# Main.net
KiCad netlist of a schematic drawn in Altium Designer
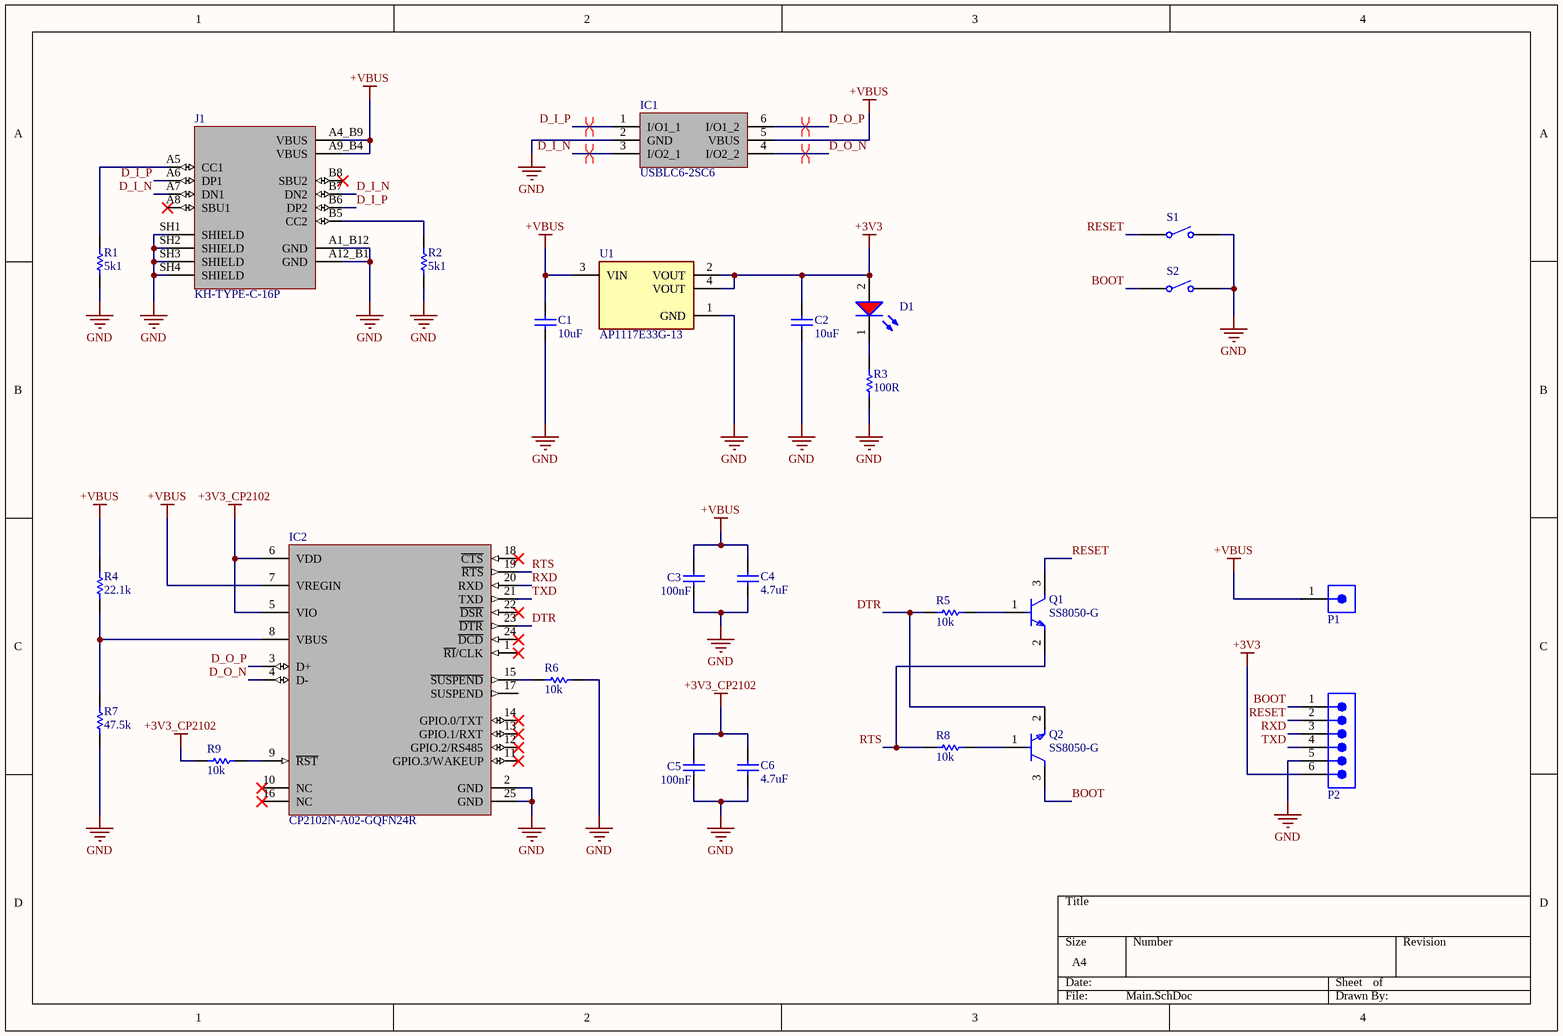
[diagram p0: Main.SchDoc]

(export (version "E")
  (design (tool "Eeschema 10.0.6"))
  (components
    (comp (ref "C1")
      (value "10uF")
      (footprint "Wurth 0603 capacitor")
      (fields (field (name "Comment") "Generic Capacitor 10uF 0603"))
      (libsource (lib "Passives") (part "Generic Capacitor 10uF 0603"))
    )
    (comp (ref "C2")
      (value "10uF")
      (footprint "Wurth 0603 capacitor")
      (fields (field (name "Comment") "Generic Capacitor 10uF 0603"))
      (libsource (lib "Passives") (part "Generic Capacitor 10uF 0603"))
    )
    (comp (ref "C3")
      (value "100nF")
      (footprint "Wurth 0603 capacitor")
      (fields (field (name "Comment") "Generic Capacitor 100nF 0603"))
      (libsource (lib "Passives") (part "Generic Capacitor 100nF 0603"))
    )
    (comp (ref "C4")
      (value "4.7uF")
      (footprint "Wurth 0603 capacitor")
      (fields (field (name "Comment") "Generic Capacitor 4.7uF 0603"))
      (libsource (lib "Passives") (part "Generic Capacitor 4.7uF 0603"))
    )
    (comp (ref "C5")
      (value "100nF")
      (footprint "Wurth 0603 capacitor")
      (fields (field (name "Comment") "Generic Capacitor 100nF 0603"))
      (libsource (lib "Passives") (part "Generic Capacitor 100nF 0603"))
    )
    (comp (ref "C6")
      (value "4.7uF")
      (footprint "Wurth 0603 capacitor")
      (fields (field (name "Comment") "Generic Capacitor 4.7uF 0603"))
      (libsource (lib "Passives") (part "Generic Capacitor 4.7uF 0603"))
    )
    (comp (ref "D1")
      (value "150060RS75000")
      (footprint "WL-SMCW_0603_150060xx75000")
      (libsource (lib "Altium Content Vault") (part "LED_Red_2A-1K"))
    )
    (comp (ref "IC1")
      (value "USBLC6-2SC6")
      (footprint "Tech Public SOT23-6")
      (description "Integrated Circuit")
      (fields (field (name "MOUSER PART NUMBER") "511-USBLC6-2SC6"))
      (libsource (lib "Diodes") (part "Tech Public USBLC6-2SC6"))
    )
    (comp (ref "IC2")
      (value "CP2102N-A02-GQFN24R")
      (footprint "Leadless:FP-CP2102N-A02-GQFN24R-IPC_C")
      (description "IC USB TO UART BRIDGE QFN24")
      (libsource (lib "USB_Controllers") (part "Silicon Labs CP2102N-A02-GQFN24R"))
    )
    (comp (ref "J1")
      (value "KH-TYPE-C-16P")
      (footprint "KINGHELM_KH-TYPE-C-16P")
      (fields (field (name "MF") "kinghelm"))
      (libsource (lib "Connectors") (part "KH-TYPE-C-16P"))
    )
    (comp (ref "P1")
      (value "61300111121")
      (footprint "1x1 2.54mm M")
      (description "WR-PHD Pin Header, THT, Vertical, pitch 2.54mm, 1 Row, 1P")
      (fields (field (name "MANUFACTURER") "Wurth Elektronik"))
      (libsource (lib "2.54mm_pin_headers") (part "1P"))
    )
    (comp (ref "P2")
      (value "61300611121")
      (footprint "6x1 2.54mm M")
      (description "WR-PHD Pin Header, THT, Vertical, pitch 2.54mm, 1 Row, 6P")
      (fields (field (name "MANUFACTURER") "Wurth Elektronik"))
      (libsource (lib "2.54mm_pin_headers") (part "6P"))
    )
    (comp (ref "Q1")
      (value "SS8050-G")
      (footprint "FP-SS8050-G-MFG")
      (description "NPN TRANSISTOR 1.5A 40V SOT-23 R")
      (libsource (lib "Altium Content Vault") (part "2a1388f82443b098dcd57d24ac7632d"))
    )
    (comp (ref "Q2")
      (value "SS8050-G")
      (footprint "FP-SS8050-G-MFG")
      (description "NPN TRANSISTOR 1.5A 40V SOT-23 R")
      (libsource (lib "Altium Content Vault") (part "2a1388f82443b098dcd57d24ac7632d"))
    )
    (comp (ref "R1")
      (value "5k1")
      (footprint "0805 Resistor")
      (fields (field (name "Comment") "Generic Resistor 5k1 0805"))
      (libsource (lib "Passives") (part "Generic Resistor 5k1 0805"))
    )
    (comp (ref "R2")
      (value "5k1")
      (footprint "0805 Resistor")
      (fields (field (name "Comment") "Generic Resistor 5k1 0805"))
      (libsource (lib "Passives") (part "Generic Resistor 5k1 0805"))
    )
    (comp (ref "R3")
      (value "100R")
      (footprint "Wurth 0603 Resistor")
      (fields (field (name "Comment") "Generic Resistor 100R 0603"))
      (libsource (lib "Passives") (part "Generic Resistor 100R 0603"))
    )
    (comp (ref "R4")
      (value "22.1k")
      (footprint "Wurth 0603 Resistor")
      (fields (field (name "Comment") "Generic Resistor 22k1 0603"))
      (libsource (lib "Passives") (part "Generic Resistor 22k1 0603"))
    )
    (comp (ref "R5")
      (value "10k")
      (footprint "Wurth 0603 Resistor")
      (fields (field (name "Comment") "Generic Resistor 10k 0603"))
      (libsource (lib "Passives") (part "Generic Resistor 10k 0603"))
    )
    (comp (ref "R6")
      (value "10k")
      (footprint "Wurth 0603 Resistor")
      (fields (field (name "Comment") "Generic Resistor 10k 0603"))
      (libsource (lib "Passives") (part "Generic Resistor 10k 0603"))
    )
    (comp (ref "R7")
      (value "47.5k")
      (footprint "Wurth 0603 Resistor")
      (fields (field (name "Comment") "Generic Resistor 47k5 0603"))
      (libsource (lib "Passives") (part "Generic Resistor 47k5 0603"))
    )
    (comp (ref "R8")
      (value "10k")
      (footprint "Wurth 0603 Resistor")
      (fields (field (name "Comment") "Generic Resistor 10k 0603"))
      (libsource (lib "Passives") (part "Generic Resistor 10k 0603"))
    )
    (comp (ref "R9")
      (value "10k")
      (footprint "Wurth 0603 Resistor")
      (fields (field (name "Comment") "Generic Resistor 10k 0603"))
      (libsource (lib "Passives") (part "Generic Resistor 10k 0603"))
    )
    (comp (ref "S1")
      (value "TS-1088R-02026")
      (footprint "TS1088R02026")
      (libsource (lib "Switches") (part "XUNPU TS-1088R-02026"))
    )
    (comp (ref "S2")
      (value "TS-1088R-02026")
      (footprint "TS1088R02026")
      (libsource (lib "Switches") (part "XUNPU TS-1088R-02026"))
    )
    (comp (ref "U1")
      (value "AP1117E33G-13")
      (footprint "FP-SOT223-MFG")
      (description "IC REG LINEAR 3.3V 1A SOT223-3")
      (fields
        (field (name "OCTOPART") "https://octopart.com/ap1117e33g-13-diodes+inc.-669494")
        (field (name "MANUFACTURER") "Diodes")
      )
      (libsource (lib "Altium Content Vault") (part "dc21beff762592c75b73352fbc679e9"))
    )
  )
  (nets
    (net (code "1") (name "+3V3") (class "Default")
      (node (ref "C2") (pin "2") (pinfunction "2_2") (pintype "passive"))
      (node (ref "D1") (pin "2") (pinfunction "A_2") (pintype "passive"))
      (node (ref "P2") (pin "6") (pinfunction "6_6") (pintype "passive"))
      (node (ref "U1") (pin "2") (pinfunction "VOUT_2") (pintype "power_in"))
      (node (ref "U1") (pin "4") (pinfunction "VOUT_4") (pintype "power_in"))
    )
    (net (code "2") (name "+3V3_CP2102") (class "Default")
      (node (ref "C5") (pin "2") (pinfunction "2_2") (pintype "passive"))
      (node (ref "C6") (pin "2") (pinfunction "2_2") (pintype "passive"))
      (node (ref "IC2") (pin "5") (pinfunction "VIO_5") (pintype "power_in"))
      (node (ref "IC2") (pin "6") (pinfunction "VDD_6") (pintype "power_in"))
      (node (ref "R9") (pin "1") (pinfunction "1_1") (pintype "passive"))
    )
    (net (code "3") (name "+VBUS") (class "Default")
      (node (ref "C1") (pin "2") (pinfunction "2_2") (pintype "passive"))
      (node (ref "C3") (pin "2") (pinfunction "2_2") (pintype "passive"))
      (node (ref "C4") (pin "2") (pinfunction "2_2") (pintype "passive"))
      (node (ref "IC1") (pin "5") (pinfunction "VBUS_5") (pintype "passive"))
      (node (ref "IC2") (pin "7") (pinfunction "VREGIN_7") (pintype "power_in"))
      (node (ref "J1") (pin "A4_B9") (pinfunction "VBUS_A4_B9") (pintype "power_in"))
      (node (ref "J1") (pin "A9_B4") (pinfunction "VBUS_A9_B4") (pintype "power_in"))
      (node (ref "P1") (pin "1") (pinfunction "1_1") (pintype "passive"))
      (node (ref "R4") (pin "2") (pinfunction "2_2") (pintype "passive"))
      (node (ref "U1") (pin "3") (pinfunction "VIN_3") (pintype "power_in"))
    )
    (net (code "4") (name "/BOOT") (class "Default")
      (node (ref "P2") (pin "1") (pinfunction "1_1") (pintype "passive"))
      (node (ref "Q2") (pin "3") (pinfunction "C_3") (pintype "passive"))
      (node (ref "S2") (pin "1") (pinfunction "1_1") (pintype "passive"))
    )
    (net (code "5") (name "/DTR") (class "Default")
      (node (ref "IC2") (pin "23") (pinfunction "~{DTR}_23") (pintype "output"))
      (node (ref "Q2") (pin "2") (pinfunction "E_2") (pintype "passive"))
      (node (ref "R5") (pin "1") (pinfunction "1_1") (pintype "passive"))
    )
    (net (code "6") (name "/D_I_N") (class "Default")
      (node (ref "IC1") (pin "3") (pinfunction "I/O2_1_3") (pintype "passive"))
      (node (ref "J1") (pin "A7") (pinfunction "DN1_A7") (pintype "bidirectional"))
      (node (ref "J1") (pin "B7") (pinfunction "DN2_B7") (pintype "bidirectional"))
    )
    (net (code "7") (name "/D_I_P") (class "Default")
      (node (ref "IC1") (pin "1") (pinfunction "I/O1_1_1") (pintype "passive"))
      (node (ref "J1") (pin "A6") (pinfunction "DP1_A6") (pintype "bidirectional"))
      (node (ref "J1") (pin "B6") (pinfunction "DP2_B6") (pintype "bidirectional"))
    )
    (net (code "8") (name "/D_O_N") (class "Default")
      (node (ref "IC1") (pin "4") (pinfunction "I/O2_2_4") (pintype "passive"))
      (node (ref "IC2") (pin "4") (pinfunction "D-_4") (pintype "bidirectional"))
    )
    (net (code "9") (name "/D_O_P") (class "Default")
      (node (ref "IC1") (pin "6") (pinfunction "I/O1_2_6") (pintype "passive"))
      (node (ref "IC2") (pin "3") (pinfunction "D+_3") (pintype "bidirectional"))
    )
    (net (code "10") (name "/RESET") (class "Default")
      (node (ref "P2") (pin "2") (pinfunction "2_2") (pintype "passive"))
      (node (ref "Q1") (pin "3") (pinfunction "C_3") (pintype "passive"))
      (node (ref "S1") (pin "1") (pinfunction "1_1") (pintype "passive"))
    )
    (net (code "11") (name "/RTS") (class "Default")
      (node (ref "IC2") (pin "19") (pinfunction "~{RTS}_19") (pintype "output"))
      (node (ref "Q1") (pin "2") (pinfunction "E_2") (pintype "passive"))
      (node (ref "R8") (pin "1") (pinfunction "1_1") (pintype "passive"))
    )
    (net (code "12") (name "/RXD") (class "Default")
      (node (ref "IC2") (pin "20") (pinfunction "RXD_20") (pintype "input"))
      (node (ref "P2") (pin "3") (pinfunction "3_3") (pintype "passive"))
    )
    (net (code "13") (name "/TXD") (class "Default")
      (node (ref "IC2") (pin "21") (pinfunction "TXD_21") (pintype "output"))
      (node (ref "P2") (pin "4") (pinfunction "4_4") (pintype "passive"))
    )
    (net (code "14") (name "GND") (class "Default")
      (node (ref "C1") (pin "1") (pinfunction "1_1") (pintype "passive"))
      (node (ref "C2") (pin "1") (pinfunction "1_1") (pintype "passive"))
      (node (ref "C3") (pin "1") (pinfunction "1_1") (pintype "passive"))
      (node (ref "C4") (pin "1") (pinfunction "1_1") (pintype "passive"))
      (node (ref "C5") (pin "1") (pinfunction "1_1") (pintype "passive"))
      (node (ref "C6") (pin "1") (pinfunction "1_1") (pintype "passive"))
      (node (ref "IC1") (pin "2") (pinfunction "GND_2") (pintype "passive"))
      (node (ref "IC2") (pin "2") (pinfunction "GND_2") (pintype "power_in"))
      (node (ref "IC2") (pin "25") (pinfunction "GND_25") (pintype "power_in"))
      (node (ref "J1") (pin "A12_B1") (pinfunction "GND_A12_B1") (pintype "power_in"))
      (node (ref "J1") (pin "A1_B12") (pinfunction "GND_A1_B12") (pintype "power_in"))
      (node (ref "J1") (pin "SH1") (pinfunction "SHIELD_SH1") (pintype "passive"))
      (node (ref "J1") (pin "SH2") (pinfunction "SHIELD_SH2") (pintype "passive"))
      (node (ref "J1") (pin "SH3") (pinfunction "SHIELD_SH3") (pintype "passive"))
      (node (ref "J1") (pin "SH4") (pinfunction "SHIELD_SH4") (pintype "passive"))
      (node (ref "P2") (pin "5") (pinfunction "5_5") (pintype "passive"))
      (node (ref "R1") (pin "1") (pinfunction "1_1") (pintype "passive"))
      (node (ref "R2") (pin "1") (pinfunction "1_1") (pintype "passive"))
      (node (ref "R3") (pin "1") (pinfunction "1_1") (pintype "passive"))
      (node (ref "R6") (pin "2") (pinfunction "2_2") (pintype "passive"))
      (node (ref "R7") (pin "1") (pinfunction "1_1") (pintype "passive"))
      (node (ref "S1") (pin "2") (pinfunction "2_2") (pintype "passive"))
      (node (ref "S2") (pin "2") (pinfunction "2_2") (pintype "passive"))
      (node (ref "U1") (pin "1") (pinfunction "GND_1") (pintype "power_in"))
    )
    (net (code "15") (name "Net-(D1-K)") (class "Default")
      (node (ref "D1") (pin "1") (pinfunction "K_1") (pintype "passive"))
      (node (ref "R3") (pin "2") (pinfunction "2_2") (pintype "passive"))
    )
    (net (code "16") (name "Net-(IC2-VBUS)") (class "Default")
      (node (ref "IC2") (pin "8") (pinfunction "VBUS_8") (pintype "power_in"))
      (node (ref "R4") (pin "1") (pinfunction "1_1") (pintype "passive"))
      (node (ref "R7") (pin "2") (pinfunction "2_2") (pintype "passive"))
    )
    (net (code "17") (name "Net-(IC2-~{RST})") (class "Default")
      (node (ref "IC2") (pin "9") (pinfunction "~{RST}_9") (pintype "input"))
      (node (ref "R9") (pin "2") (pinfunction "2_2") (pintype "passive"))
    )
    (net (code "18") (name "Net-(IC2-~{SUSPEND})") (class "Default")
      (node (ref "IC2") (pin "15") (pinfunction "~{SUSPEND}_15") (pintype "output"))
      (node (ref "R6") (pin "1") (pinfunction "1_1") (pintype "passive"))
    )
    (net (code "19") (name "Net-(J1-CC1)") (class "Default")
      (node (ref "J1") (pin "A5") (pinfunction "CC1_A5") (pintype "bidirectional"))
      (node (ref "R1") (pin "2") (pinfunction "2_2") (pintype "passive"))
    )
    (net (code "20") (name "Net-(J1-CC2)") (class "Default")
      (node (ref "J1") (pin "B5") (pinfunction "CC2_B5") (pintype "bidirectional"))
      (node (ref "R2") (pin "2") (pinfunction "2_2") (pintype "passive"))
    )
    (net (code "21") (name "Net-(Q1-B)") (class "Default")
      (node (ref "Q1") (pin "1") (pinfunction "B_1") (pintype "passive"))
      (node (ref "R5") (pin "2") (pinfunction "2_2") (pintype "passive"))
    )
    (net (code "22") (name "Net-(Q2-B)") (class "Default")
      (node (ref "Q2") (pin "1") (pinfunction "B_1") (pintype "passive"))
      (node (ref "R8") (pin "2") (pinfunction "2_2") (pintype "passive"))
    )
    (net (code "23") (name "unconnected-(IC2-GPIO.0{slash}TXT-Pad14)") (class "Default")
      (node (ref "IC2") (pin "14") (pinfunction "GPIO.0/TXT_14") (pintype "bidirectional+no_connect"))
    )
    (net (code "24") (name "unconnected-(IC2-GPIO.1{slash}RXT-Pad13)") (class "Default")
      (node (ref "IC2") (pin "13") (pinfunction "GPIO.1/RXT_13") (pintype "bidirectional+no_connect"))
    )
    (net (code "25") (name "unconnected-(IC2-GPIO.2{slash}RS485-Pad12)") (class "Default")
      (node (ref "IC2") (pin "12") (pinfunction "GPIO.2/RS485_12") (pintype "bidirectional+no_connect"))
    )
    (net (code "26") (name "unconnected-(IC2-GPIO.3{slash}WAKEUP-Pad11)") (class "Default")
      (node (ref "IC2") (pin "11") (pinfunction "GPIO.3/WAKEUP_11") (pintype "bidirectional+no_connect"))
    )
    (net (code "27") (name "unconnected-(IC2-NC-Pad10)") (class "Default")
      (node (ref "IC2") (pin "10") (pinfunction "NC_10") (pintype "passive+no_connect"))
    )
    (net (code "28") (name "unconnected-(IC2-NC-Pad16)") (class "Default")
      (node (ref "IC2") (pin "16") (pinfunction "NC_16") (pintype "passive+no_connect"))
    )
    (net (code "29") (name "unconnected-(IC2-SUSPEND-Pad17)") (class "Default")
      (node (ref "IC2") (pin "17") (pinfunction "SUSPEND_17") (pintype "output"))
    )
    (net (code "30") (name "unconnected-(IC2-~{CTS}-Pad18)") (class "Default")
      (node (ref "IC2") (pin "18") (pinfunction "~{CTS}_18") (pintype "input+no_connect"))
    )
    (net (code "31") (name "unconnected-(IC2-~{DCD}-Pad24)") (class "Default")
      (node (ref "IC2") (pin "24") (pinfunction "~{DCD}_24") (pintype "input+no_connect"))
    )
    (net (code "32") (name "unconnected-(IC2-~{DSR}-Pad22)") (class "Default")
      (node (ref "IC2") (pin "22") (pinfunction "~{DSR}_22") (pintype "input+no_connect"))
    )
    (net (code "33") (name "unconnected-(IC2-~{RI}{slash}CLK-Pad1)") (class "Default")
      (node (ref "IC2") (pin "1") (pinfunction "~{RI}/CLK_1") (pintype "input+no_connect"))
    )
    (net (code "34") (name "unconnected-(J1-SBU1-PadA8)") (class "Default")
      (node (ref "J1") (pin "A8") (pinfunction "SBU1_A8") (pintype "bidirectional+no_connect"))
    )
    (net (code "35") (name "unconnected-(J1-SBU2-PadB8)") (class "Default")
      (node (ref "J1") (pin "B8") (pinfunction "SBU2_B8") (pintype "bidirectional+no_connect"))
    )
  )
)
